# SCH_PROJET_SAE_2025.net
KiCad netlist of a schematic drawn in EasyEDA
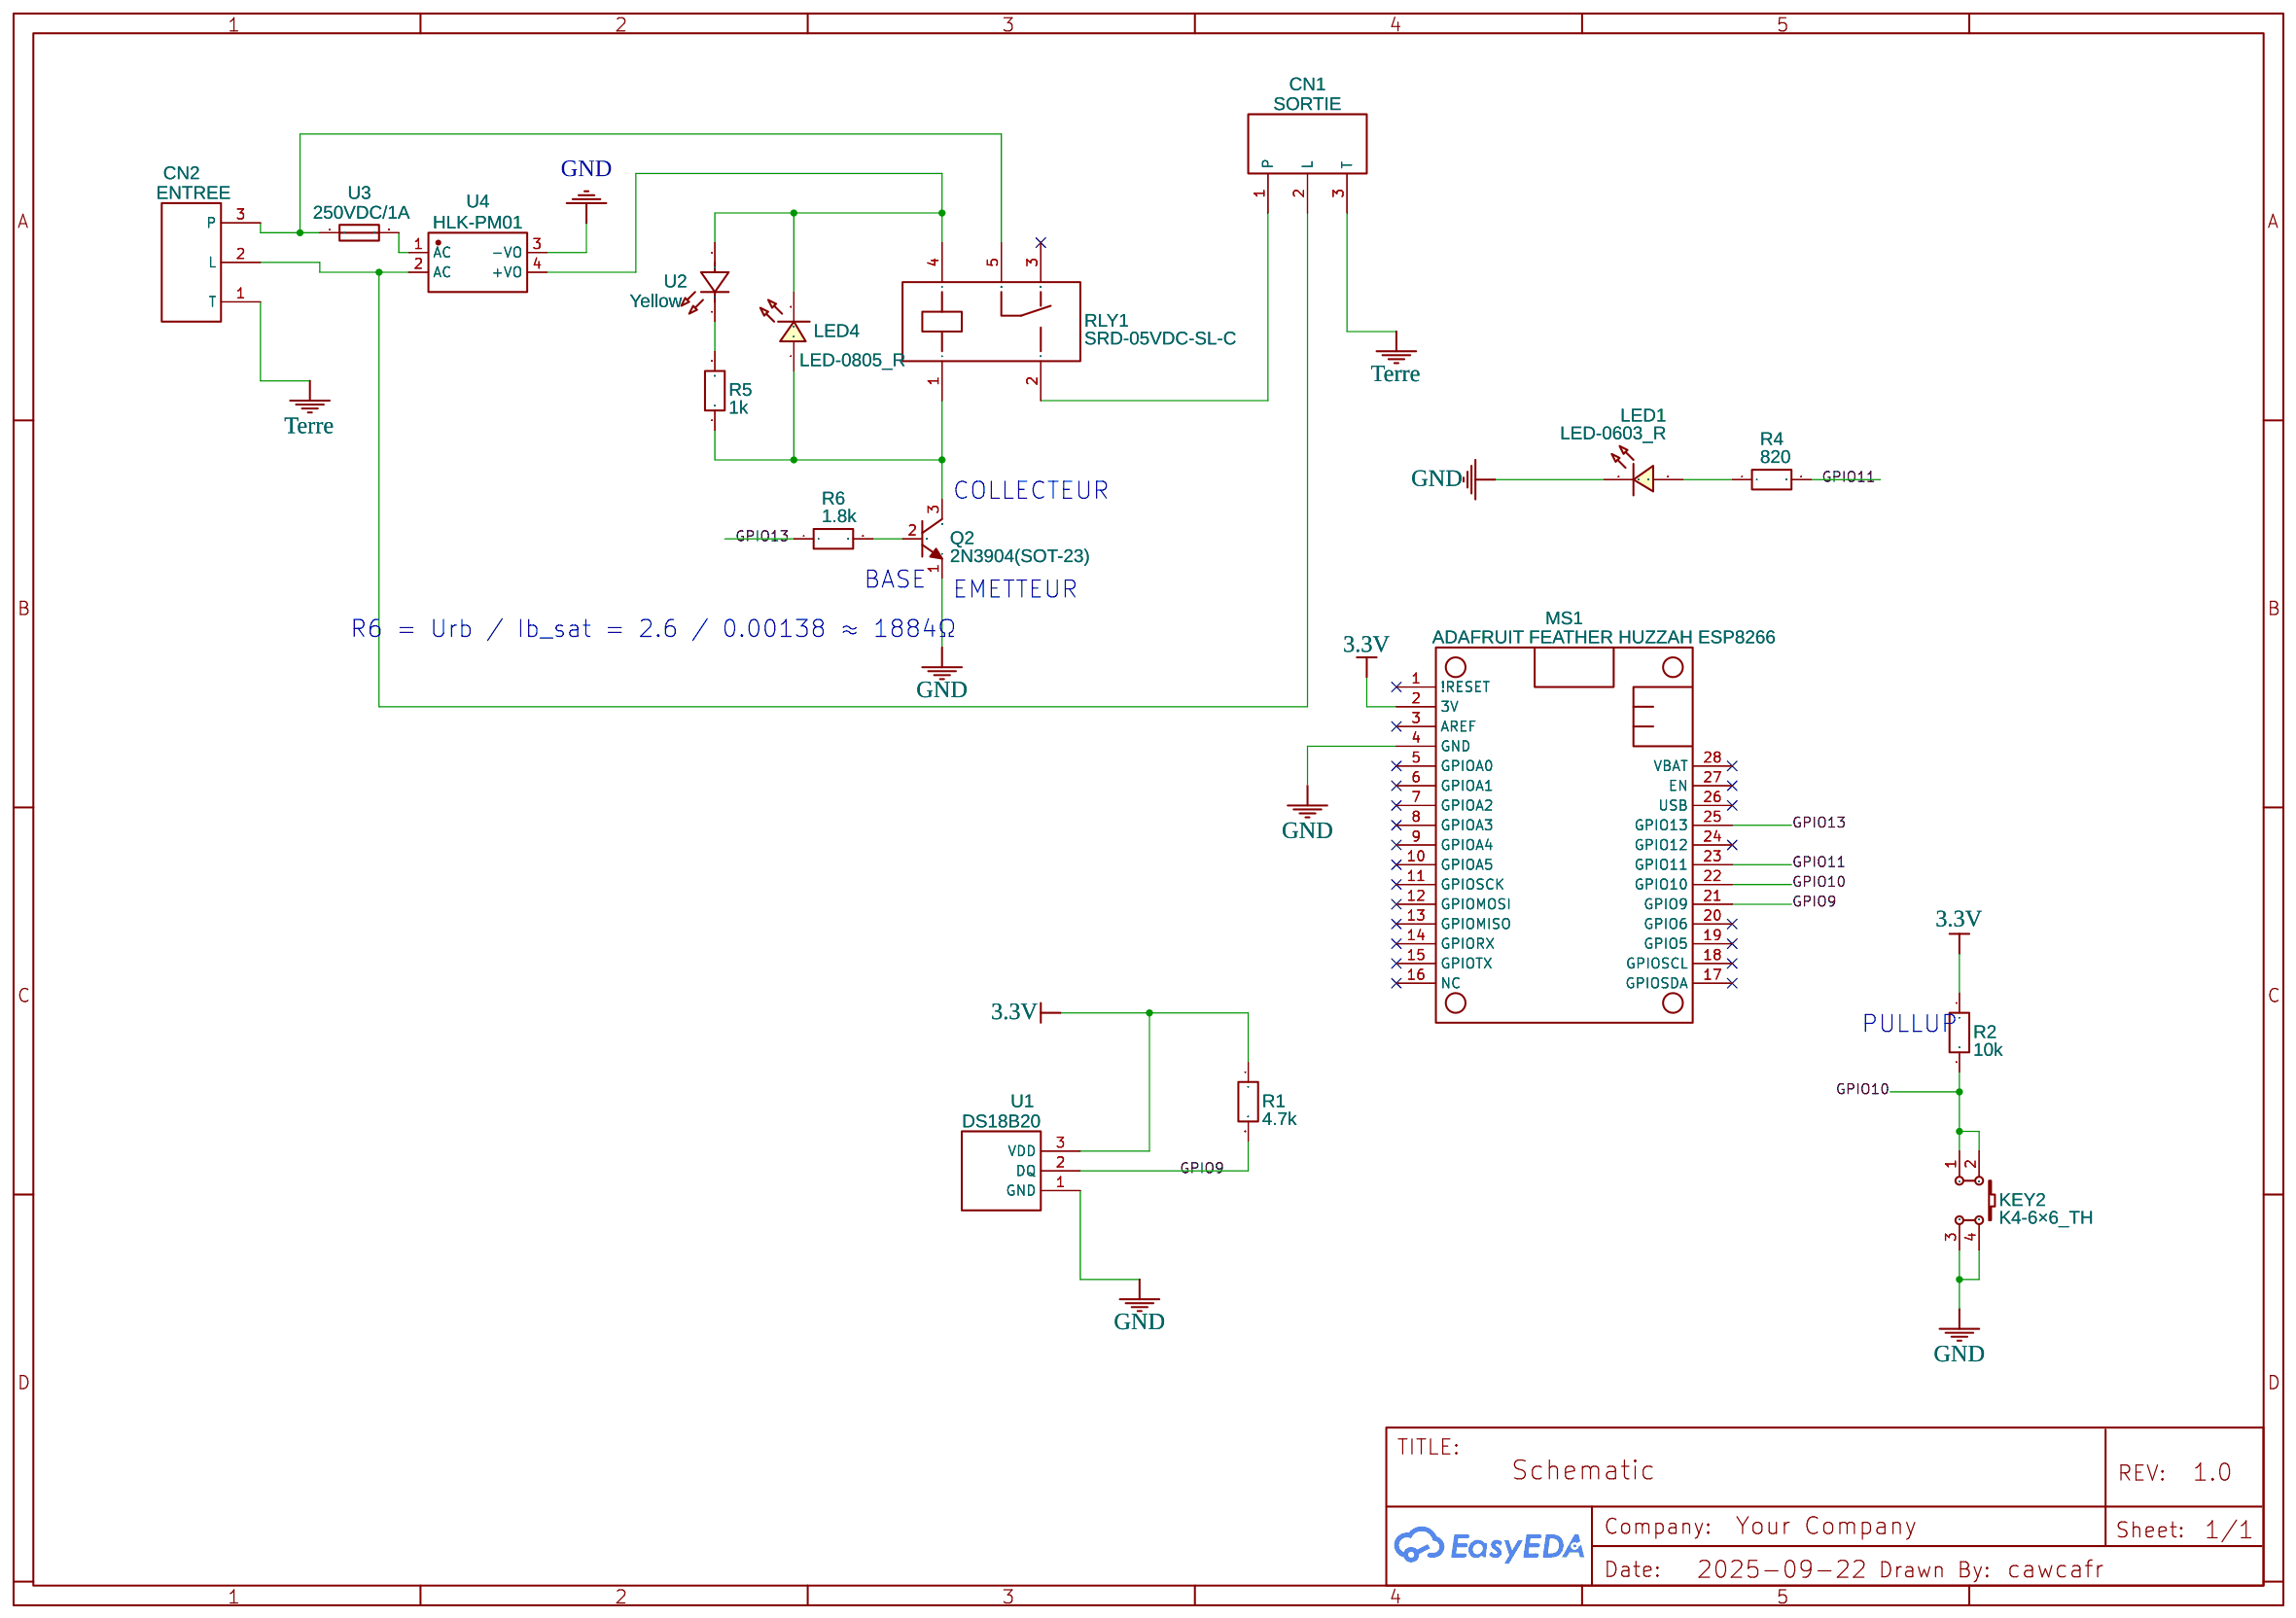
[diagram p0: schematic sheet]

(export (version "E")
  (design (tool "Eeschema 10.0.6"))
  (components
    (comp (ref "CN1")
      (value "SORTIE")
      (fields
        (field (name "Manufacturer Part") "1729131")
        (field (name "Manufacturer") "Phoenix Contact(菲尼克斯)")
      )
      (libsource (lib "") (part "MKDSN1.5/3-5.08_1"))
    )
    (comp (ref "CN2")
      (value "ENTREE")
      (fields
        (field (name "Manufacturer Part") "1729131")
        (field (name "Manufacturer") "Phoenix Contact(菲尼克斯)")
      )
      (libsource (lib "") (part "MKDSN1.5/3-5.08"))
    )
    (comp (ref "KEY2")
      (value "K4-6×6_TH")
      (fields (field (name "Manufacturer Part") "K2-1102DP-E4SW-04") (field (name "Manufacturer") "韩国韩荣"))
      (libsource (lib "") (part "K4-6×6_TH"))
    )
    (comp (ref "LED1")
      (value "LED-0603_R")
      (fields
        (field (name "Manufacturer Part") "19-217/R6C-AL1M2VY/3T")
        (field (name "Manufacturer") "EVERLIGHT(台湾亿光)")
      )
      (libsource (lib "") (part "LED-0603_R"))
    )
    (comp (ref "LED4")
      (value "LED-0805_R")
      (fields
        (field (name "Manufacturer Part") "17-21SURC/S530-A3/TR8")
        (field (name "Manufacturer") "EVERLIGHT(台湾亿光)")
      )
      (libsource (lib "") (part "LED-0805_R"))
    )
    (comp (ref "MS1")
      (value "ADAFRUIT FEATHER HUZZAH ESP8266")
      (libsource (lib "") (part "ADAFRUIT FEATHER HUZZAH ESP8266"))
    )
    (comp (ref "Q2")
      (value "2N3904(SOT-23)")
      (fields (field (name "Manufacturer Part") "2n3904S-RTK/PS") (field (name "Manufacturer") "KEC"))
      (libsource (lib "") (part "2N3904(SOT-23)"))
    )
    (comp (ref "R1") (value "4.7k") (libsource (lib "") (part "R_0805_EU")))
    (comp (ref "R2") (value "10k") (libsource (lib "") (part "R_0805_EU")))
    (comp (ref "R4") (value "820") (libsource (lib "") (part "R_0805_EU_1")))
    (comp (ref "R5") (value "1k") (libsource (lib "") (part "R_0805_EU_2")))
    (comp (ref "R6") (value "1.8k") (libsource (lib "") (part "R_0805_EU_1")))
    (comp (ref "RLY1")
      (value "SRD-05VDC-SL-C")
      (fields (field (name "Manufacturer") "松乐"))
      (libsource (lib "") (part "SRD-05VDC-SL-C"))
    )
    (comp (ref "U1") (value "DS18B20") (libsource (lib "") (part "DS18B20")))
    (comp (ref "U2")
      (value "Yellow")
      (fields (field (name "Manufacturer Part") "0603"))
      (libsource (lib "") (part "0603"))
    )
    (comp (ref "U3")
      (value "250VDC/1A")
      (fields (field (name "Manufacturer Part") "30VDC/4A"))
      (libsource (lib "") (part "30VDC/4A"))
    )
    (comp (ref "U4")
      (value "HLK-PM01")
      (fields (field (name "Manufacturer") "HI-LINK(海凌科)"))
      (libsource (lib "") (part "HLK-PM01"))
    )
  )
  (nets
    (net (code "1") (name "/GPIO9") (class "Default")
      (node (ref "MS1") (pin "21") (pinfunction "GPIO9_21") (pintype "unspecified"))
      (node (ref "R1") (pin "2") (pinfunction "2_2") (pintype "unspecified"))
      (node (ref "U1") (pin "2") (pinfunction "DQ_2") (pintype "unspecified"))
    )
    (net (code "2") (name "/GPIO10") (class "Default")
      (node (ref "KEY2") (pin "1") (pinfunction "1_1") (pintype "unspecified"))
      (node (ref "KEY2") (pin "2") (pinfunction "2_2") (pintype "unspecified"))
      (node (ref "MS1") (pin "22") (pinfunction "GPIO10_22") (pintype "unspecified"))
      (node (ref "R2") (pin "2") (pinfunction "2_2") (pintype "unspecified"))
    )
    (net (code "3") (name "/GPIO11") (class "Default")
      (node (ref "MS1") (pin "23") (pinfunction "GPIO11_23") (pintype "unspecified"))
      (node (ref "R4") (pin "2") (pinfunction "2_2") (pintype "unspecified"))
    )
    (net (code "4") (name "/GPIO13") (class "Default")
      (node (ref "MS1") (pin "25") (pinfunction "GPIO13_25") (pintype "unspecified"))
      (node (ref "R6") (pin "1") (pinfunction "1_1") (pintype "unspecified"))
    )
    (net (code "5") (name "3.3V") (class "Default")
      (node (ref "MS1") (pin "2") (pinfunction "3V_2") (pintype "unspecified"))
      (node (ref "R1") (pin "1") (pinfunction "1_1") (pintype "unspecified"))
      (node (ref "R2") (pin "1") (pinfunction "1_1") (pintype "unspecified"))
      (node (ref "U1") (pin "3") (pinfunction "VDD_3") (pintype "unspecified"))
    )
    (net (code "6") (name "GND") (class "Default")
      (node (ref "KEY2") (pin "3") (pinfunction "3_3") (pintype "unspecified"))
      (node (ref "KEY2") (pin "4") (pinfunction "4_4") (pintype "unspecified"))
      (node (ref "LED1") (pin "2") (pinfunction "2_2") (pintype "unspecified"))
      (node (ref "MS1") (pin "4") (pinfunction "GND_4") (pintype "passive"))
      (node (ref "Q2") (pin "1") (pinfunction "E_1") (pintype "input"))
      (node (ref "U1") (pin "1") (pinfunction "GND_1") (pintype "unspecified"))
      (node (ref "U4") (pin "3") (pinfunction "-VO_3") (pintype "unspecified"))
    )
    (net (code "7") (name "Net-(CN1-L)") (class "Default")
      (node (ref "CN1") (pin "2") (pinfunction "L_2") (pintype "unspecified"))
      (node (ref "CN2") (pin "2") (pinfunction "L_2") (pintype "unspecified"))
      (node (ref "U4") (pin "2") (pinfunction "AC_2") (pintype "unspecified"))
    )
    (net (code "8") (name "Net-(CN1-P)") (class "Default")
      (node (ref "CN1") (pin "1") (pinfunction "P_1") (pintype "unspecified"))
      (node (ref "RLY1") (pin "2") (pinfunction "2_2") (pintype "input"))
    )
    (net (code "9") (name "Net-(CN2-P)") (class "Default")
      (node (ref "CN2") (pin "3") (pinfunction "P_3") (pintype "unspecified"))
      (node (ref "RLY1") (pin "5") (pinfunction "5_5") (pintype "input"))
      (node (ref "U3") (pin "1") (pinfunction "1_1") (pintype "unspecified"))
    )
    (net (code "10") (name "Net-(LED1-Pad1)") (class "Default")
      (node (ref "LED1") (pin "1") (pinfunction "1_1") (pintype "unspecified"))
      (node (ref "R4") (pin "1") (pinfunction "1_1") (pintype "unspecified"))
    )
    (net (code "11") (name "Net-(Q2-B)") (class "Default")
      (node (ref "Q2") (pin "2") (pinfunction "B_2") (pintype "input"))
      (node (ref "R6") (pin "2") (pinfunction "2_2") (pintype "unspecified"))
    )
    (net (code "12") (name "Net-(Q2-C)") (class "Default")
      (node (ref "LED4") (pin "1") (pinfunction "1_1") (pintype "unspecified"))
      (node (ref "Q2") (pin "3") (pinfunction "C_3") (pintype "input"))
      (node (ref "R5") (pin "1") (pinfunction "1_1") (pintype "unspecified"))
      (node (ref "RLY1") (pin "1") (pinfunction "1_1") (pintype "input"))
    )
    (net (code "13") (name "Net-(U2-A)") (class "Default")
      (node (ref "LED4") (pin "2") (pinfunction "2_2") (pintype "unspecified"))
      (node (ref "RLY1") (pin "4") (pinfunction "4_4") (pintype "input"))
      (node (ref "U2") (pin "2") (pinfunction "A_2") (pintype "unspecified"))
      (node (ref "U4") (pin "4") (pinfunction "+VO_4") (pintype "unspecified"))
    )
    (net (code "14") (name "Net-(U2-K)") (class "Default")
      (node (ref "R5") (pin "2") (pinfunction "2_2") (pintype "unspecified"))
      (node (ref "U2") (pin "1") (pinfunction "K_1") (pintype "unspecified"))
    )
    (net (code "15") (name "Net-(U3-Pad2)") (class "Default")
      (node (ref "U3") (pin "2") (pinfunction "2_2") (pintype "unspecified"))
      (node (ref "U4") (pin "1") (pinfunction "AC_1") (pintype "unspecified"))
    )
    (net (code "16") (name "Terre") (class "Default")
      (node (ref "CN1") (pin "3") (pinfunction "T_3") (pintype "unspecified"))
      (node (ref "CN2") (pin "1") (pinfunction "T_1") (pintype "unspecified"))
    )
    (net (code "17") (name "unconnected-(MS1-!RESET-Pad1)") (class "Default")
      (node (ref "MS1") (pin "1") (pinfunction "!RESET_1") (pintype "input+no_connect"))
    )
    (net (code "18") (name "unconnected-(MS1-AREF-Pad3)") (class "Default")
      (node (ref "MS1") (pin "3") (pinfunction "AREF_3") (pintype "unspecified+no_connect"))
    )
    (net (code "19") (name "unconnected-(MS1-EN-Pad27)") (class "Default")
      (node (ref "MS1") (pin "27") (pinfunction "EN_27") (pintype "unspecified+no_connect"))
    )
    (net (code "20") (name "unconnected-(MS1-GPIO5-Pad19)") (class "Default")
      (node (ref "MS1") (pin "19") (pinfunction "GPIO5_19") (pintype "unspecified+no_connect"))
    )
    (net (code "21") (name "unconnected-(MS1-GPIO6-Pad20)") (class "Default")
      (node (ref "MS1") (pin "20") (pinfunction "GPIO6_20") (pintype "unspecified+no_connect"))
    )
    (net (code "22") (name "unconnected-(MS1-GPIO12-Pad24)") (class "Default")
      (node (ref "MS1") (pin "24") (pinfunction "GPIO12_24") (pintype "unspecified+no_connect"))
    )
    (net (code "23") (name "unconnected-(MS1-GPIOA0-Pad5)") (class "Default")
      (node (ref "MS1") (pin "5") (pinfunction "GPIOA0_5") (pintype "unspecified+no_connect"))
    )
    (net (code "24") (name "unconnected-(MS1-GPIOA1-Pad6)") (class "Default")
      (node (ref "MS1") (pin "6") (pinfunction "GPIOA1_6") (pintype "unspecified+no_connect"))
    )
    (net (code "25") (name "unconnected-(MS1-GPIOA2-Pad7)") (class "Default")
      (node (ref "MS1") (pin "7") (pinfunction "GPIOA2_7") (pintype "unspecified+no_connect"))
    )
    (net (code "26") (name "unconnected-(MS1-GPIOA3-Pad8)") (class "Default")
      (node (ref "MS1") (pin "8") (pinfunction "GPIOA3_8") (pintype "unspecified+no_connect"))
    )
    (net (code "27") (name "unconnected-(MS1-GPIOA4-Pad9)") (class "Default")
      (node (ref "MS1") (pin "9") (pinfunction "GPIOA4_9") (pintype "unspecified+no_connect"))
    )
    (net (code "28") (name "unconnected-(MS1-GPIOA5-Pad10)") (class "Default")
      (node (ref "MS1") (pin "10") (pinfunction "GPIOA5_10") (pintype "unspecified+no_connect"))
    )
    (net (code "29") (name "unconnected-(MS1-GPIOMISO-Pad13)") (class "Default")
      (node (ref "MS1") (pin "13") (pinfunction "GPIOMISO_13") (pintype "unspecified+no_connect"))
    )
    (net (code "30") (name "unconnected-(MS1-GPIOMOSI-Pad12)") (class "Default")
      (node (ref "MS1") (pin "12") (pinfunction "GPIOMOSI_12") (pintype "unspecified+no_connect"))
    )
    (net (code "31") (name "unconnected-(MS1-GPIORX-Pad14)") (class "Default")
      (node (ref "MS1") (pin "14") (pinfunction "GPIORX_14") (pintype "unspecified+no_connect"))
    )
    (net (code "32") (name "unconnected-(MS1-GPIOSCK-Pad11)") (class "Default")
      (node (ref "MS1") (pin "11") (pinfunction "GPIOSCK_11") (pintype "unspecified+no_connect"))
    )
    (net (code "33") (name "unconnected-(MS1-GPIOSCL-Pad18)") (class "Default")
      (node (ref "MS1") (pin "18") (pinfunction "GPIOSCL_18") (pintype "unspecified+no_connect"))
    )
    (net (code "34") (name "unconnected-(MS1-GPIOSDA-Pad17)") (class "Default")
      (node (ref "MS1") (pin "17") (pinfunction "GPIOSDA_17") (pintype "unspecified+no_connect"))
    )
    (net (code "35") (name "unconnected-(MS1-GPIOTX-Pad15)") (class "Default")
      (node (ref "MS1") (pin "15") (pinfunction "GPIOTX_15") (pintype "unspecified+no_connect"))
    )
    (net (code "36") (name "unconnected-(MS1-NC-Pad16)") (class "Default")
      (node (ref "MS1") (pin "16") (pinfunction "NC_16") (pintype "unspecified+no_connect"))
    )
    (net (code "37") (name "unconnected-(MS1-USB-Pad26)") (class "Default")
      (node (ref "MS1") (pin "26") (pinfunction "USB_26") (pintype "unspecified+no_connect"))
    )
    (net (code "38") (name "unconnected-(MS1-VBAT-Pad28)") (class "Default")
      (node (ref "MS1") (pin "28") (pinfunction "VBAT_28") (pintype "unspecified+no_connect"))
    )
    (net (code "39") (name "unconnected-(RLY1-Pad3)") (class "Default")
      (node (ref "RLY1") (pin "3") (pinfunction "3_3") (pintype "input+no_connect"))
    )
  )
)
